# rx_315mhz.net
KiCad netlist of a schematic drawn in EAGLE
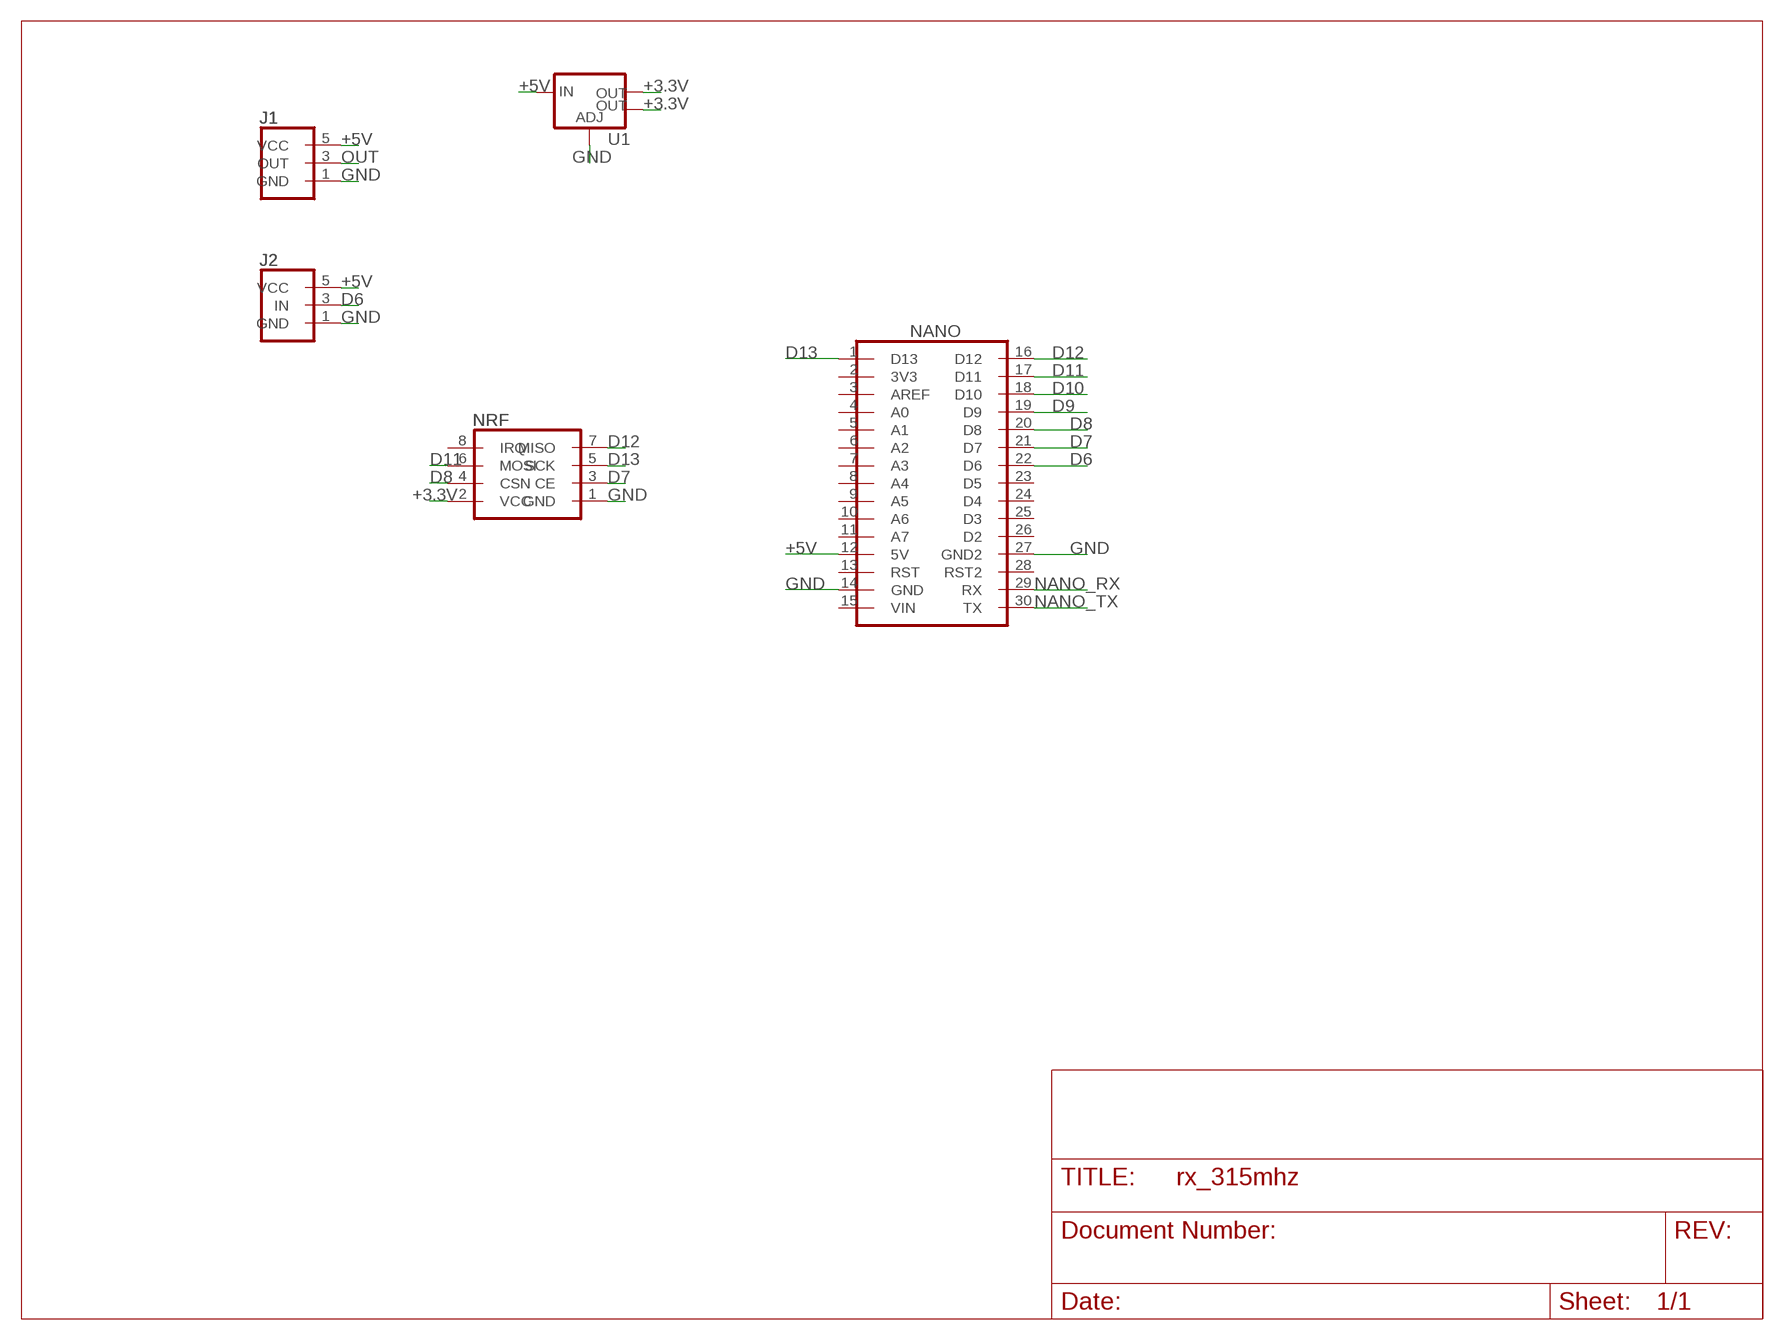
[diagram p0: schematic, sheet 1]

(export (version "E")
  (design (tool "Eeschema 10.0.6"))
  (components
    (comp (ref "J1")
      (value "OUT_HEAD_3BIG")
      (footprint "eagle-import:OUT_HEAD_3_BIG")
      (libsource (lib "eagle-import") (part "OUT_HEAD_3BIG"))
    )
    (comp (ref "J2")
      (value "315MHZ_TX")
      (footprint "eagle-import:315MHZ_TX")
      (libsource (lib "eagle-import") (part "315MHZ_TX"))
    )
    (comp (ref "NANO")
      (value "ARDUINO_NANO")
      (footprint "eagle-import:ARDUINO_NANO")
      (libsource (lib "eagle-import") (part "ARDUINO_NANO"))
    )
    (comp (ref "NRF")
      (value "NRF24L01_MODULE")
      (footprint "eagle-import:NRF24L01")
      (libsource (lib "eagle-import") (part "NRF24L01_MODULE"))
    )
    (comp (ref "U1")
      (value "V_REG_LM1117SOT223")
      (footprint "eagle-import:SOT223")
      (libsource (lib "eagle-import") (part "V_REG_LM1117SOT223"))
    )
  )
  (nets
    (net (code "1") (name "/+3.3V") (class "Default")
      (node (ref "NRF") (pin "2") (pinfunction "VCC_2") (pintype "bidirectional"))
      (node (ref "U1") (pin "2") (pinfunction "OUT_2") (pintype "output"))
      (node (ref "U1") (pin "4") (pinfunction "OUT_4") (pintype "output"))
    )
    (net (code "2") (name "/+5V") (class "Default")
      (node (ref "J1") (pin "5") (pinfunction "VCC_5") (pintype "bidirectional"))
      (node (ref "J2") (pin "5") (pinfunction "VCC_5") (pintype "bidirectional"))
      (node (ref "NANO") (pin "12") (pinfunction "5V_12") (pintype "bidirectional"))
      (node (ref "U1") (pin "3") (pinfunction "IN_3") (pintype "input"))
    )
    (net (code "3") (name "/D6") (class "Default")
      (node (ref "J2") (pin "3") (pinfunction "IN_3") (pintype "bidirectional"))
      (node (ref "NANO") (pin "22") (pinfunction "D6_22") (pintype "bidirectional"))
    )
    (net (code "4") (name "/D7") (class "Default")
      (node (ref "NANO") (pin "21") (pinfunction "D7_21") (pintype "bidirectional"))
      (node (ref "NRF") (pin "3") (pinfunction "CE_3") (pintype "bidirectional"))
    )
    (net (code "5") (name "/D8") (class "Default")
      (node (ref "NANO") (pin "20") (pinfunction "D8_20") (pintype "bidirectional"))
      (node (ref "NRF") (pin "4") (pinfunction "CSN_4") (pintype "bidirectional"))
    )
    (net (code "6") (name "/D9") (class "Default")
      (node (ref "NANO") (pin "19") (pinfunction "D9_19") (pintype "bidirectional"))
    )
    (net (code "7") (name "/D10") (class "Default")
      (node (ref "NANO") (pin "18") (pinfunction "D10_18") (pintype "bidirectional"))
    )
    (net (code "8") (name "/D11") (class "Default")
      (node (ref "NANO") (pin "17") (pinfunction "D11_17") (pintype "bidirectional"))
      (node (ref "NRF") (pin "6") (pinfunction "MOSI_6") (pintype "bidirectional"))
    )
    (net (code "9") (name "/D12") (class "Default")
      (node (ref "NANO") (pin "16") (pinfunction "D12_16") (pintype "bidirectional"))
      (node (ref "NRF") (pin "7") (pinfunction "MISO_7") (pintype "bidirectional"))
    )
    (net (code "10") (name "/D13") (class "Default")
      (node (ref "NANO") (pin "1") (pinfunction "D13_1") (pintype "bidirectional"))
      (node (ref "NRF") (pin "5") (pinfunction "SCK_5") (pintype "bidirectional"))
    )
    (net (code "11") (name "/GND") (class "Default")
      (node (ref "J1") (pin "1") (pinfunction "GND_1") (pintype "bidirectional"))
      (node (ref "J2") (pin "1") (pinfunction "GND_1") (pintype "bidirectional"))
      (node (ref "NANO") (pin "14") (pinfunction "GND_14") (pintype "bidirectional"))
      (node (ref "NANO") (pin "27") (pinfunction "GND2_27") (pintype "bidirectional"))
      (node (ref "NRF") (pin "1") (pinfunction "GND_1") (pintype "bidirectional"))
      (node (ref "U1") (pin "1") (pinfunction "ADJ_1") (pintype "input"))
    )
    (net (code "12") (name "/NANO_RX") (class "Default")
      (node (ref "NANO") (pin "29") (pinfunction "RX_29") (pintype "bidirectional"))
    )
    (net (code "13") (name "/NANO_TX") (class "Default")
      (node (ref "NANO") (pin "30") (pinfunction "TX_30") (pintype "bidirectional"))
    )
    (net (code "14") (name "/OUT") (class "Default")
      (node (ref "J1") (pin "3") (pinfunction "OUT_3") (pintype "bidirectional"))
    )
    (net (code "15") (name "unconnected-(NANO-3V3-Pad2)") (class "Default")
      (node (ref "NANO") (pin "2") (pinfunction "3V3_2") (pintype "bidirectional"))
    )
    (net (code "16") (name "unconnected-(NANO-A0-Pad4)") (class "Default")
      (node (ref "NANO") (pin "4") (pinfunction "A0_4") (pintype "bidirectional"))
    )
    (net (code "17") (name "unconnected-(NANO-A1-Pad5)") (class "Default")
      (node (ref "NANO") (pin "5") (pinfunction "A1_5") (pintype "bidirectional"))
    )
    (net (code "18") (name "unconnected-(NANO-A2-Pad6)") (class "Default")
      (node (ref "NANO") (pin "6") (pinfunction "A2_6") (pintype "bidirectional"))
    )
    (net (code "19") (name "unconnected-(NANO-A3-Pad7)") (class "Default")
      (node (ref "NANO") (pin "7") (pinfunction "A3_7") (pintype "bidirectional"))
    )
    (net (code "20") (name "unconnected-(NANO-A4-Pad8)") (class "Default")
      (node (ref "NANO") (pin "8") (pinfunction "A4_8") (pintype "bidirectional"))
    )
    (net (code "21") (name "unconnected-(NANO-A5-Pad9)") (class "Default")
      (node (ref "NANO") (pin "9") (pinfunction "A5_9") (pintype "bidirectional"))
    )
    (net (code "22") (name "unconnected-(NANO-A6-Pad10)") (class "Default")
      (node (ref "NANO") (pin "10") (pinfunction "A6_10") (pintype "bidirectional"))
    )
    (net (code "23") (name "unconnected-(NANO-A7-Pad11)") (class "Default")
      (node (ref "NANO") (pin "11") (pinfunction "A7_11") (pintype "bidirectional"))
    )
    (net (code "24") (name "unconnected-(NANO-AREF-Pad3)") (class "Default")
      (node (ref "NANO") (pin "3") (pinfunction "AREF_3") (pintype "bidirectional"))
    )
    (net (code "25") (name "unconnected-(NANO-D2-Pad26)") (class "Default")
      (node (ref "NANO") (pin "26") (pinfunction "D2_26") (pintype "bidirectional"))
    )
    (net (code "26") (name "unconnected-(NANO-D3-Pad25)") (class "Default")
      (node (ref "NANO") (pin "25") (pinfunction "D3_25") (pintype "bidirectional"))
    )
    (net (code "27") (name "unconnected-(NANO-D4-Pad24)") (class "Default")
      (node (ref "NANO") (pin "24") (pinfunction "D4_24") (pintype "bidirectional"))
    )
    (net (code "28") (name "unconnected-(NANO-D5-Pad23)") (class "Default")
      (node (ref "NANO") (pin "23") (pinfunction "D5_23") (pintype "bidirectional"))
    )
    (net (code "29") (name "unconnected-(NANO-RST-Pad13)") (class "Default")
      (node (ref "NANO") (pin "13") (pinfunction "RST_13") (pintype "bidirectional"))
    )
    (net (code "30") (name "unconnected-(NANO-RST2-Pad28)") (class "Default")
      (node (ref "NANO") (pin "28") (pinfunction "RST2_28") (pintype "bidirectional"))
    )
    (net (code "31") (name "unconnected-(NANO-VIN-Pad15)") (class "Default")
      (node (ref "NANO") (pin "15") (pinfunction "VIN_15") (pintype "bidirectional"))
    )
    (net (code "32") (name "unconnected-(NRF-IRQ-Pad8)") (class "Default")
      (node (ref "NRF") (pin "8") (pinfunction "IRQ_8") (pintype "bidirectional"))
    )
  )
)
